# System.net
KiCad netlist of a schematic drawn in Altium Designer
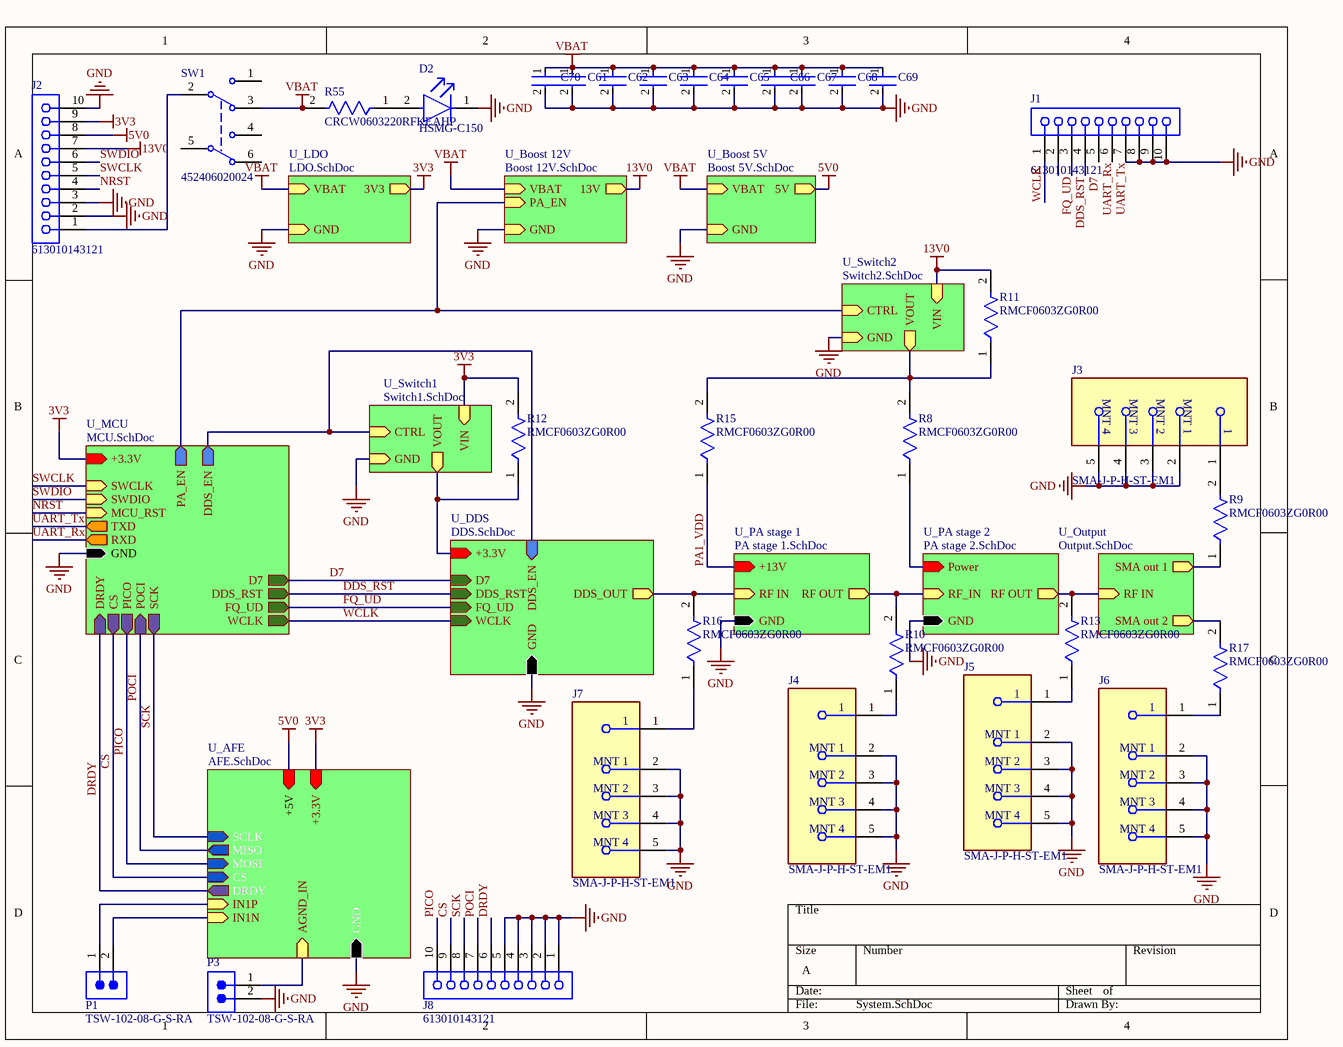
[diagram p0: System.SchDoc]

(export (version "E")
  (design (tool "Eeschema 10.0.6"))
  (components
    (comp (ref "C61")
      (value "GRM21BR60J107ME15K")
      (footprint "FP-GRM21B-0_2-e0_2_0_7-IPC_B")
      (description "Chip Multilayer Ceramic Capacitors for General Purpose, 0805, 100uF, X5R, 15%, 20%, 6.3V")
      (fields (field (name "TOLERANCE") "20%"))
      (libsource (lib "Altium Content Vault") (part "b4654b650e69147ec39a6b967a45e02"))
    )
    (comp (ref "C62")
      (value "GRM21BR60J107ME15K")
      (footprint "FP-GRM21B-0_2-e0_2_0_7-IPC_B")
      (description "Chip Multilayer Ceramic Capacitors for General Purpose, 0805, 100uF, X5R, 15%, 20%, 6.3V")
      (fields (field (name "TOLERANCE") "20%"))
      (libsource (lib "Altium Content Vault") (part "b4654b650e69147ec39a6b967a45e02"))
    )
    (comp (ref "C63")
      (value "GRM21BR60J107ME15K")
      (footprint "FP-GRM21B-0_2-e0_2_0_7-IPC_B")
      (description "Chip Multilayer Ceramic Capacitors for General Purpose, 0805, 100uF, X5R, 15%, 20%, 6.3V")
      (fields (field (name "TOLERANCE") "20%"))
      (libsource (lib "Altium Content Vault") (part "b4654b650e69147ec39a6b967a45e02"))
    )
    (comp (ref "C64")
      (value "GRM21BR60J107ME15K")
      (footprint "FP-GRM21B-0_2-e0_2_0_7-IPC_B")
      (description "Chip Multilayer Ceramic Capacitors for General Purpose, 0805, 100uF, X5R, 15%, 20%, 6.3V")
      (fields (field (name "TOLERANCE") "20%"))
      (libsource (lib "Altium Content Vault") (part "b4654b650e69147ec39a6b967a45e02"))
    )
    (comp (ref "C65")
      (value "GRM21BR60J107ME15K")
      (footprint "FP-GRM21B-0_2-e0_2_0_7-IPC_B")
      (description "Chip Multilayer Ceramic Capacitors for General Purpose, 0805, 100uF, X5R, 15%, 20%, 6.3V")
      (fields (field (name "TOLERANCE") "20%"))
      (libsource (lib "Altium Content Vault") (part "b4654b650e69147ec39a6b967a45e02"))
    )
    (comp (ref "C66")
      (value "GRM21BR60J107ME15K")
      (footprint "FP-GRM21B-0_2-e0_2_0_7-IPC_B")
      (description "Chip Multilayer Ceramic Capacitors for General Purpose, 0805, 100uF, X5R, 15%, 20%, 6.3V")
      (fields (field (name "TOLERANCE") "20%"))
      (libsource (lib "Altium Content Vault") (part "b4654b650e69147ec39a6b967a45e02"))
    )
    (comp (ref "C67")
      (value "GRM21BR60J107ME15K")
      (footprint "FP-GRM21B-0_2-e0_2_0_7-IPC_B")
      (description "Chip Multilayer Ceramic Capacitors for General Purpose, 0805, 100uF, X5R, 15%, 20%, 6.3V")
      (fields (field (name "TOLERANCE") "20%"))
      (libsource (lib "Altium Content Vault") (part "b4654b650e69147ec39a6b967a45e02"))
    )
    (comp (ref "C68")
      (value "GRM21BR60J107ME15K")
      (footprint "FP-GRM21B-0_2-e0_2_0_7-IPC_B")
      (description "Chip Multilayer Ceramic Capacitors for General Purpose, 0805, 100uF, X5R, 15%, 20%, 6.3V")
      (fields (field (name "TOLERANCE") "20%"))
      (libsource (lib "Altium Content Vault") (part "b4654b650e69147ec39a6b967a45e02"))
    )
    (comp (ref "C69")
      (value "GRM21BR60J107ME15K")
      (footprint "FP-GRM21B-0_2-e0_2_0_7-IPC_B")
      (description "Chip Multilayer Ceramic Capacitors for General Purpose, 0805, 100uF, X5R, 15%, 20%, 6.3V")
      (fields (field (name "TOLERANCE") "20%"))
      (libsource (lib "Altium Content Vault") (part "b4654b650e69147ec39a6b967a45e02"))
    )
    (comp (ref "C70")
      (value "GRM21BR60J107ME15K")
      (footprint "FP-GRM21B-0_2-e0_2_0_7-IPC_B")
      (description "Chip Multilayer Ceramic Capacitors for General Purpose, 0805, 100uF, X5R, 15%, 20%, 6.3V")
      (fields (field (name "TOLERANCE") "20%"))
      (libsource (lib "Altium Content Vault") (part "b4654b650e69147ec39a6b967a45e02"))
    )
    (comp (ref "D2")
      (value "HSMG-C150")
      (footprint "FP-HSMG-C150-MFG")
      (description "LED GREEN DIFFUSED 1206 SMD")
      (fields
        (field (name "MANUFACTURER") "Broadcom")
        (field (name "OCTOPART") "https://octopart.com/hsmg-c150-broadcom-71131304")
      )
      (libsource (lib "Altium Content Vault") (part "8706943c75ba83719d021d2fdc84c58"))
    )
    (comp (ref "J1")
      (value "613010143121")
      (footprint "613010143121")
      (libsource (lib "Altium Content Vault") (part "Header_Female_1R_10P"))
    )
    (comp (ref "J2")
      (value "613010143121")
      (footprint "613010143121")
      (libsource (lib "Altium Content Vault") (part "Header_Female_1R_10P"))
    )
    (comp (ref "J3")
      (value "SMA-J-P-H-ST-EM1")
      (footprint "FP-SMA-J-P-H-ST-EM1-MFG")
      (description "CONN SMA JACK STR 50OHM EDGE MNT")
      (libsource (lib "") (part "c65b8a639cdaef1819ea20b5466f8fa_1"))
    )
    (comp (ref "J4")
      (value "SMA-J-P-H-ST-EM1")
      (footprint "FP-SMA-J-P-H-ST-EM1-MFG")
      (description "CONN SMA JACK STR 50OHM EDGE MNT")
      (libsource (lib "Altium Content Vault") (part "c65b8a639cdaef1819ea20b5466f8fa"))
    )
    (comp (ref "J5")
      (value "SMA-J-P-H-ST-EM1")
      (footprint "FP-SMA-J-P-H-ST-EM1-MFG")
      (description "CONN SMA JACK STR 50OHM EDGE MNT")
      (libsource (lib "Altium Content Vault") (part "c65b8a639cdaef1819ea20b5466f8fa"))
    )
    (comp (ref "J6")
      (value "SMA-J-P-H-ST-EM1")
      (footprint "FP-SMA-J-P-H-ST-EM1-MFG")
      (description "CONN SMA JACK STR 50OHM EDGE MNT")
      (libsource (lib "Altium Content Vault") (part "c65b8a639cdaef1819ea20b5466f8fa"))
    )
    (comp (ref "J7")
      (value "SMA-J-P-H-ST-EM1")
      (footprint "FP-SMA-J-P-H-ST-EM1-MFG")
      (description "CONN SMA JACK STR 50OHM EDGE MNT")
      (libsource (lib "Altium Content Vault") (part "c65b8a639cdaef1819ea20b5466f8fa"))
    )
    (comp (ref "J8")
      (value "613010143121")
      (footprint "613010143121")
      (libsource (lib "Altium Content Vault") (part "Header_Female_1R_10P"))
    )
    (comp (ref "P1")
      (value "TSW-102-08-G-S-RA")
      (footprint "SMTC-TSW-102-08-X-S-RA")
      (fields (field (name "MANUFACTURER") "Samtec"))
      (libsource (lib "Altium Content Vault") (part "SMTC-TSW-102-X-X-S-X"))
    )
    (comp (ref "P3")
      (value "TSW-102-08-G-S-RA")
      (footprint "SMTC-TSW-102-08-X-S-RA")
      (fields (field (name "MANUFACTURER") "Samtec"))
      (libsource (lib "Altium Content Vault") (part "SMTC-TSW-102-X-X-S-X"))
    )
    (comp (ref "R8")
      (value "RMCF0603ZG0R00")
      (footprint "FP-RMCF0603-IPC_B")
      (description "0Ω ±0 0.1W 0603 Thick Film Chip Resistor AEC-Q200 compliant")
      (libsource (lib "Altium Content Vault") (part "1029c3af85768c4190bb7ad29bc67b5"))
    )
    (comp (ref "R9")
      (value "RMCF0603ZG0R00")
      (footprint "FP-RMCF0603-IPC_B")
      (description "0Ω ±0 0.1W 0603 Thick Film Chip Resistor AEC-Q200 compliant")
      (libsource (lib "Altium Content Vault") (part "1029c3af85768c4190bb7ad29bc67b5"))
    )
    (comp (ref "R10")
      (value "RMCF0603ZG0R00")
      (footprint "FP-RMCF0603-IPC_B")
      (description "0Ω ±0 0.1W 0603 Thick Film Chip Resistor AEC-Q200 compliant")
      (libsource (lib "Altium Content Vault") (part "1029c3af85768c4190bb7ad29bc67b5"))
    )
    (comp (ref "R11")
      (value "RMCF0603ZG0R00")
      (footprint "FP-RMCF0603-IPC_B")
      (description "0Ω ±0 0.1W 0603 Thick Film Chip Resistor AEC-Q200 compliant")
      (libsource (lib "Altium Content Vault") (part "1029c3af85768c4190bb7ad29bc67b5"))
    )
    (comp (ref "R12")
      (value "RMCF0603ZG0R00")
      (footprint "FP-RMCF0603-IPC_B")
      (description "0Ω ±0 0.1W 0603 Thick Film Chip Resistor AEC-Q200 compliant")
      (libsource (lib "Altium Content Vault") (part "1029c3af85768c4190bb7ad29bc67b5"))
    )
    (comp (ref "R13")
      (value "RMCF0603ZG0R00")
      (footprint "FP-RMCF0603-IPC_B")
      (description "0Ω ±0 0.1W 0603 Thick Film Chip Resistor AEC-Q200 compliant")
      (libsource (lib "Altium Content Vault") (part "1029c3af85768c4190bb7ad29bc67b5"))
    )
    (comp (ref "R15")
      (value "RMCF0603ZG0R00")
      (footprint "FP-RMCF0603-IPC_B")
      (description "0Ω ±0 0.1W 0603 Thick Film Chip Resistor AEC-Q200 compliant")
      (libsource (lib "Altium Content Vault") (part "1029c3af85768c4190bb7ad29bc67b5"))
    )
    (comp (ref "R16")
      (value "RMCF0603ZG0R00")
      (footprint "FP-RMCF0603-IPC_B")
      (description "0Ω ±0 0.1W 0603 Thick Film Chip Resistor AEC-Q200 compliant")
      (libsource (lib "Altium Content Vault") (part "1029c3af85768c4190bb7ad29bc67b5"))
    )
    (comp (ref "R17")
      (value "RMCF0603ZG0R00")
      (footprint "FP-RMCF0603-IPC_B")
      (description "0Ω ±0 0.1W 0603 Thick Film Chip Resistor AEC-Q200 compliant")
      (libsource (lib "Altium Content Vault") (part "1029c3af85768c4190bb7ad29bc67b5"))
    )
    (comp (ref "R55")
      (value "CRCW0603220RFKEAHP")
      (footprint "FP-CRCW0603-HPe3-IPC_A")
      (description "RES Thick Film, 220Ω, 1%, 0.33W, 100ppm/°C, 0603")
      (fields (field (name "TOLERANCE") "1%"))
      (libsource (lib "Altium Content Vault") (part "1029c3af85768c4190bb7ad29bc67b5"))
    )
    (comp (ref "SW1")
      (value "452406020024")
      (footprint "452406020024")
      (description "Ws-slsv_smt Mini Slide Switch Sa")
      (libsource (lib "Altium Content Vault") (part "DPDT_WS-SLSV"))
    )
  )
  (nets
    (net (code "1") (name "/AGND_IN") (class "Default")
      (node (ref "P3") (pin "1") (pinfunction "1_1") (pintype "passive"))
    )
    (net (code "2") (name "/CS") (class "Default")
      (node (ref "J8") (pin "9") (pinfunction "9_9") (pintype "passive"))
    )
    (net (code "3") (name "/D7") (class "Default")
      (node (ref "J1") (pin "4") (pinfunction "4_4") (pintype "passive"))
    )
    (net (code "5") (name "/DDS_OUT") (class "Default")
      (node (ref "R16") (pin "2") (pinfunction "2_2") (pintype "passive"))
    )
    (net (code "6") (name "/DDS_RST") (class "Default")
      (node (ref "J1") (pin "3") (pinfunction "3_3") (pintype "passive"))
    )
    (net (code "7") (name "/DRDY") (class "Default")
      (node (ref "J8") (pin "6") (pinfunction "6_6") (pintype "passive"))
    )
    (net (code "8") (name "/FQ_UD") (class "Default")
      (node (ref "J1") (pin "2") (pinfunction "2_2") (pintype "passive"))
    )
    (net (code "9") (name "/IN1N") (class "Default")
      (node (ref "P1") (pin "2") (pinfunction "2_2") (pintype "passive"))
    )
    (net (code "10") (name "/IN1P") (class "Default")
      (node (ref "P1") (pin "1") (pinfunction "1_1") (pintype "passive"))
    )
    (net (code "11") (name "/NRST") (class "Default")
      (node (ref "J2") (pin "4") (pinfunction "4_4") (pintype "passive"))
    )
    (net (code "12") (name "/PA1_VDD") (class "Default")
      (node (ref "R15") (pin "1") (pinfunction "1_1") (pintype "passive"))
    )
    (net (code "14") (name "/PICO") (class "Default")
      (node (ref "J8") (pin "10") (pinfunction "10_10") (pintype "passive"))
    )
    (net (code "15") (name "/POCI") (class "Default")
      (node (ref "J8") (pin "7") (pinfunction "7_7") (pintype "passive"))
    )
    (net (code "16") (name "/Power") (class "Default")
      (node (ref "R8") (pin "1") (pinfunction "1_1") (pintype "passive"))
    )
    (net (code "17") (name "/RF OUT") (class "Default")
      (node (ref "R13") (pin "2") (pinfunction "2_2") (pintype "passive"))
    )
    (net (code "18") (name "/RF OUT_1") (class "Default")
      (node (ref "R10") (pin "2") (pinfunction "2_2") (pintype "passive"))
    )
    (net (code "19") (name "/SCK") (class "Default")
      (node (ref "J8") (pin "8") (pinfunction "8_8") (pintype "passive"))
    )
    (net (code "20") (name "/SMA out 1") (class "Default")
      (node (ref "R9") (pin "1") (pinfunction "1_1") (pintype "passive"))
    )
    (net (code "21") (name "/SMA out 2") (class "Default")
      (node (ref "R17") (pin "2") (pinfunction "2_2") (pintype "passive"))
    )
    (net (code "22") (name "/SWCLK") (class "Default")
      (node (ref "J2") (pin "5") (pinfunction "5_5") (pintype "passive"))
    )
    (net (code "23") (name "/SWDIO") (class "Default")
      (node (ref "J2") (pin "6") (pinfunction "6_6") (pintype "passive"))
    )
    (net (code "24") (name "/UART_Rx") (class "Default")
      (node (ref "J1") (pin "5") (pinfunction "5_5") (pintype "passive"))
    )
    (net (code "25") (name "/UART_Tx") (class "Default")
      (node (ref "J1") (pin "6") (pinfunction "6_6") (pintype "passive"))
    )
    (net (code "26") (name "/VOUT") (class "Default")
      (node (ref "R12") (pin "1") (pinfunction "1_1") (pintype "passive"))
    )
    (net (code "27") (name "/VOUT_1") (class "Default")
      (node (ref "R11") (pin "1") (pinfunction "1_1") (pintype "passive"))
      (node (ref "R15") (pin "2") (pinfunction "2_2") (pintype "passive"))
      (node (ref "R8") (pin "2") (pinfunction "2_2") (pintype "passive"))
    )
    (net (code "28") (name "/WCLK") (class "Default")
      (node (ref "J1") (pin "1") (pinfunction "1_1") (pintype "passive"))
    )
    (net (code "29") (name "3V3") (class "Default")
      (node (ref "J2") (pin "9") (pinfunction "9_9") (pintype "passive"))
      (node (ref "R12") (pin "2") (pinfunction "2_2") (pintype "passive"))
    )
    (net (code "30") (name "5V0") (class "Default")
      (node (ref "J2") (pin "8") (pinfunction "8_8") (pintype "passive"))
    )
    (net (code "31") (name "13V0") (class "Default")
      (node (ref "J2") (pin "7") (pinfunction "7_7") (pintype "passive"))
      (node (ref "R11") (pin "2") (pinfunction "2_2") (pintype "passive"))
    )
    (net (code "32") (name "GND") (class "Default")
      (node (ref "C61") (pin "2") (pinfunction "2_2") (pintype "passive"))
      (node (ref "C62") (pin "2") (pinfunction "2_2") (pintype "passive"))
      (node (ref "C63") (pin "2") (pinfunction "2_2") (pintype "passive"))
      (node (ref "C64") (pin "2") (pinfunction "2_2") (pintype "passive"))
      (node (ref "C65") (pin "2") (pinfunction "2_2") (pintype "passive"))
      (node (ref "C66") (pin "2") (pinfunction "2_2") (pintype "passive"))
      (node (ref "C67") (pin "2") (pinfunction "2_2") (pintype "passive"))
      (node (ref "C68") (pin "2") (pinfunction "2_2") (pintype "passive"))
      (node (ref "C69") (pin "2") (pinfunction "2_2") (pintype "passive"))
      (node (ref "C70") (pin "2") (pinfunction "2_2") (pintype "passive"))
      (node (ref "D2") (pin "1") (pinfunction "C_1") (pintype "passive"))
      (node (ref "J1") (pin "10") (pinfunction "10_10") (pintype "passive"))
      (node (ref "J1") (pin "7") (pinfunction "7_7") (pintype "passive"))
      (node (ref "J1") (pin "8") (pinfunction "8_8") (pintype "passive"))
      (node (ref "J1") (pin "9") (pinfunction "9_9") (pintype "passive"))
      (node (ref "J2") (pin "10") (pinfunction "10_10") (pintype "passive"))
      (node (ref "J2") (pin "2") (pinfunction "2_2") (pintype "passive"))
      (node (ref "J2") (pin "3") (pinfunction "3_3") (pintype "passive"))
      (node (ref "J3") (pin "2") (pinfunction "MNT_1_2") (pintype "passive"))
      (node (ref "J3") (pin "3") (pinfunction "MNT_2_3") (pintype "passive"))
      (node (ref "J3") (pin "4") (pinfunction "MNT_3_4") (pintype "passive"))
      (node (ref "J3") (pin "5") (pinfunction "MNT_4_5") (pintype "passive"))
      (node (ref "J4") (pin "2") (pinfunction "MNT_1_2") (pintype "passive"))
      (node (ref "J4") (pin "3") (pinfunction "MNT_2_3") (pintype "passive"))
      (node (ref "J4") (pin "4") (pinfunction "MNT_3_4") (pintype "passive"))
      (node (ref "J4") (pin "5") (pinfunction "MNT_4_5") (pintype "passive"))
      (node (ref "J5") (pin "2") (pinfunction "MNT_1_2") (pintype "passive"))
      (node (ref "J5") (pin "3") (pinfunction "MNT_2_3") (pintype "passive"))
      (node (ref "J5") (pin "4") (pinfunction "MNT_3_4") (pintype "passive"))
      (node (ref "J5") (pin "5") (pinfunction "MNT_4_5") (pintype "passive"))
      (node (ref "J6") (pin "2") (pinfunction "MNT_1_2") (pintype "passive"))
      (node (ref "J6") (pin "3") (pinfunction "MNT_2_3") (pintype "passive"))
      (node (ref "J6") (pin "4") (pinfunction "MNT_3_4") (pintype "passive"))
      (node (ref "J6") (pin "5") (pinfunction "MNT_4_5") (pintype "passive"))
      (node (ref "J7") (pin "2") (pinfunction "MNT_1_2") (pintype "passive"))
      (node (ref "J7") (pin "3") (pinfunction "MNT_2_3") (pintype "passive"))
      (node (ref "J7") (pin "4") (pinfunction "MNT_3_4") (pintype "passive"))
      (node (ref "J7") (pin "5") (pinfunction "MNT_4_5") (pintype "passive"))
      (node (ref "J8") (pin "1") (pinfunction "1_1") (pintype "passive"))
      (node (ref "J8") (pin "2") (pinfunction "2_2") (pintype "passive"))
      (node (ref "J8") (pin "3") (pinfunction "3_3") (pintype "passive"))
      (node (ref "J8") (pin "4") (pinfunction "4_4") (pintype "passive"))
      (node (ref "J8") (pin "5") (pinfunction "5_5") (pintype "passive"))
      (node (ref "P3") (pin "2") (pinfunction "2_2") (pintype "passive"))
    )
    (net (code "33") (name "Net-(D2-A)") (class "Default")
      (node (ref "D2") (pin "2") (pinfunction "A_2") (pintype "passive"))
      (node (ref "R55") (pin "1") (pinfunction "1_1") (pintype "passive"))
    )
    (net (code "34") (name "Net-(J2-Pad1)") (class "Default")
      (node (ref "J2") (pin "1") (pinfunction "1_1") (pintype "passive"))
      (node (ref "SW1") (pin "2") (pinfunction "COM_2") (pintype "passive"))
    )
    (net (code "35") (name "Net-(J3-Pad1)") (class "Default")
      (node (ref "J3") (pin "1") (pinfunction "1_1") (pintype "passive"))
      (node (ref "R9") (pin "2") (pinfunction "2_2") (pintype "passive"))
    )
    (net (code "36") (name "Net-(J4-Pad1)") (class "Default")
      (node (ref "J4") (pin "1") (pinfunction "1_1") (pintype "passive"))
      (node (ref "R10") (pin "1") (pinfunction "1_1") (pintype "passive"))
    )
    (net (code "37") (name "Net-(J5-Pad1)") (class "Default")
      (node (ref "J5") (pin "1") (pinfunction "1_1") (pintype "passive"))
      (node (ref "R13") (pin "1") (pinfunction "1_1") (pintype "passive"))
    )
    (net (code "38") (name "Net-(J6-Pad1)") (class "Default")
      (node (ref "J6") (pin "1") (pinfunction "1_1") (pintype "passive"))
      (node (ref "R17") (pin "1") (pinfunction "1_1") (pintype "passive"))
    )
    (net (code "39") (name "Net-(J7-Pad1)") (class "Default")
      (node (ref "J7") (pin "1") (pinfunction "1_1") (pintype "passive"))
      (node (ref "R16") (pin "1") (pinfunction "1_1") (pintype "passive"))
    )
    (net (code "40") (name "VBAT") (class "Default")
      (node (ref "C61") (pin "1") (pinfunction "1_1") (pintype "passive"))
      (node (ref "C62") (pin "1") (pinfunction "1_1") (pintype "passive"))
      (node (ref "C63") (pin "1") (pinfunction "1_1") (pintype "passive"))
      (node (ref "C64") (pin "1") (pinfunction "1_1") (pintype "passive"))
      (node (ref "C65") (pin "1") (pinfunction "1_1") (pintype "passive"))
      (node (ref "C66") (pin "1") (pinfunction "1_1") (pintype "passive"))
      (node (ref "C67") (pin "1") (pinfunction "1_1") (pintype "passive"))
      (node (ref "C68") (pin "1") (pinfunction "1_1") (pintype "passive"))
      (node (ref "C69") (pin "1") (pinfunction "1_1") (pintype "passive"))
      (node (ref "C70") (pin "1") (pinfunction "1_1") (pintype "passive"))
      (node (ref "R55") (pin "2") (pinfunction "2_2") (pintype "passive"))
      (node (ref "SW1") (pin "3") (pinfunction "3_3") (pintype "passive"))
    )
    (net (code "41") (name "unconnected-(SW1-COM-Pad5)") (class "Default")
      (node (ref "SW1") (pin "5") (pinfunction "COM_5") (pintype "passive"))
    )
    (net (code "42") (name "unconnected-(SW1-Pad1)") (class "Default")
      (node (ref "SW1") (pin "1") (pinfunction "1_1") (pintype "passive"))
    )
    (net (code "43") (name "unconnected-(SW1-Pad4)") (class "Default")
      (node (ref "SW1") (pin "4") (pinfunction "4_4") (pintype "passive"))
    )
    (net (code "44") (name "unconnected-(SW1-Pad6)") (class "Default")
      (node (ref "SW1") (pin "6") (pinfunction "6_6") (pintype "passive"))
    )
  )
)
